# DC3402.net
KiCad netlist of a schematic drawn in EAGLE
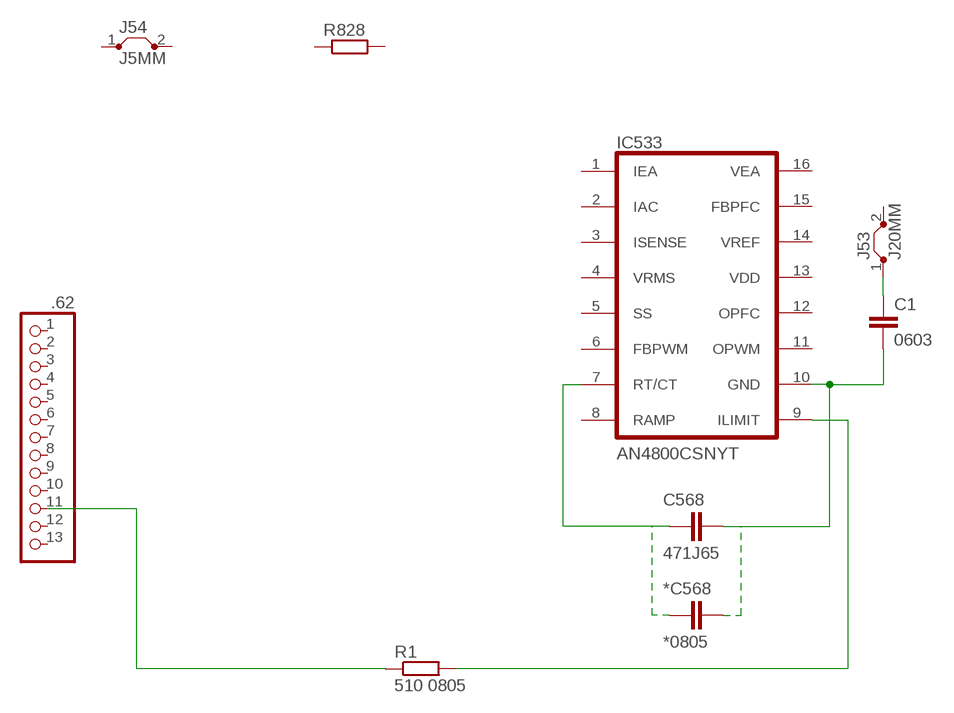
[diagram p0: schematic, sheet 1]

(export (version "E")
  (design (tool "Eeschema 10.0.6"))
  (components
    (comp (ref "*C568")
      (value "*0805")
      (footprint "eagle-import:C0805")
      (libsource (lib "eagle-import") (part "C-EUC0805"))
    )
    (comp (ref ".62")
      (value "PINHD-1X13/90")
      (footprint "eagle-import:1X13_90")
      (libsource (lib "eagle-import") (part "PINHD-1X13/90"))
    )
    (comp (ref "C1")
      (value "0603")
      (footprint "eagle-import:C0603")
      (libsource (lib "eagle-import") (part "C-EUC0603"))
    )
    (comp (ref "C568")
      (value "471J65")
      (footprint "eagle-import:C025-025X050")
      (libsource (lib "eagle-import") (part "C-EU025-025X050"))
    )
    (comp (ref "IC533")
      (value "AN4800CSNYT")
      (footprint "eagle-import:DIL16")
      (libsource (lib "eagle-import") (part "FAN4800"))
    )
    (comp (ref "J53")
      (value "J20MM")
      (footprint "eagle-import:20")
      (libsource (lib "eagle-import") (part "J20MM"))
    )
    (comp (ref "J54")
      (value "J5MM")
      (footprint "eagle-import:05")
      (libsource (lib "eagle-import") (part "J5MM"))
    )
    (comp (ref "R1")
      (value "510 0805")
      (footprint "eagle-import:R0805")
      (libsource (lib "eagle-import") (part "R-EU_R0805"))
    )
    (comp (ref "R828")
      (value "R-EU_0207/12")
      (footprint "eagle-import:0207_12")
      (libsource (lib "eagle-import") (part "R-EU_0207/12"))
    )
  )
  (nets
    (net (code "1") (name "Net-(.62-Pad11)") (class "Default")
      (node (ref ".62") (pin "11") (pinfunction "11_11") (pintype "passive"))
      (node (ref "R1") (pin "1") (pinfunction "1_1") (pintype "passive"))
    )
    (net (code "2") (name "Net-(C1-Pad1)") (class "Default")
      (node (ref "C1") (pin "1") (pinfunction "1_1") (pintype "passive"))
      (node (ref "J53") (pin "1") (pinfunction "1_1") (pintype "passive"))
    )
    (net (code "3") (name "Net-(IC533-GND)") (class "Default")
      (node (ref "*C568") (pin "2") (pinfunction "2_2") (pintype "passive"))
      (node (ref "C1") (pin "2") (pinfunction "2_2") (pintype "passive"))
      (node (ref "C568") (pin "2") (pinfunction "2_2") (pintype "passive"))
      (node (ref "IC533") (pin "10") (pinfunction "GND_10") (pintype "bidirectional"))
    )
    (net (code "4") (name "Net-(IC533-ILIMIT)") (class "Default")
      (node (ref "IC533") (pin "9") (pinfunction "ILIMIT_9") (pintype "bidirectional"))
      (node (ref "R1") (pin "2") (pinfunction "2_2") (pintype "passive"))
    )
    (net (code "5") (name "Net-(IC533-RT{slash}CT)") (class "Default")
      (node (ref "*C568") (pin "1") (pinfunction "1_1") (pintype "passive"))
      (node (ref "C568") (pin "1") (pinfunction "1_1") (pintype "passive"))
      (node (ref "IC533") (pin "7") (pinfunction "RT/CT_7") (pintype "bidirectional"))
    )
    (net (code "6") (name "unconnected-(.62-Pad1)") (class "Default")
      (node (ref ".62") (pin "1") (pinfunction "1_1") (pintype "passive"))
    )
    (net (code "7") (name "unconnected-(.62-Pad2)") (class "Default")
      (node (ref ".62") (pin "2") (pinfunction "2_2") (pintype "passive"))
    )
    (net (code "8") (name "unconnected-(.62-Pad3)") (class "Default")
      (node (ref ".62") (pin "3") (pinfunction "3_3") (pintype "passive"))
    )
    (net (code "9") (name "unconnected-(.62-Pad4)") (class "Default")
      (node (ref ".62") (pin "4") (pinfunction "4_4") (pintype "passive"))
    )
    (net (code "10") (name "unconnected-(.62-Pad5)") (class "Default")
      (node (ref ".62") (pin "5") (pinfunction "5_5") (pintype "passive"))
    )
    (net (code "11") (name "unconnected-(.62-Pad6)") (class "Default")
      (node (ref ".62") (pin "6") (pinfunction "6_6") (pintype "passive"))
    )
    (net (code "12") (name "unconnected-(.62-Pad7)") (class "Default")
      (node (ref ".62") (pin "7") (pinfunction "7_7") (pintype "passive"))
    )
    (net (code "13") (name "unconnected-(.62-Pad8)") (class "Default")
      (node (ref ".62") (pin "8") (pinfunction "8_8") (pintype "passive"))
    )
    (net (code "14") (name "unconnected-(.62-Pad9)") (class "Default")
      (node (ref ".62") (pin "9") (pinfunction "9_9") (pintype "passive"))
    )
    (net (code "15") (name "unconnected-(.62-Pad10)") (class "Default")
      (node (ref ".62") (pin "10") (pinfunction "10_10") (pintype "passive"))
    )
    (net (code "16") (name "unconnected-(.62-Pad12)") (class "Default")
      (node (ref ".62") (pin "12") (pinfunction "12_12") (pintype "passive"))
    )
    (net (code "17") (name "unconnected-(.62-Pad13)") (class "Default")
      (node (ref ".62") (pin "13") (pinfunction "13_13") (pintype "passive"))
    )
    (net (code "18") (name "unconnected-(IC533-FBPFC-Pad15)") (class "Default")
      (node (ref "IC533") (pin "15") (pinfunction "FBPFC_15") (pintype "bidirectional"))
    )
    (net (code "19") (name "unconnected-(IC533-FBPWM-Pad6)") (class "Default")
      (node (ref "IC533") (pin "6") (pinfunction "FBPWM_6") (pintype "bidirectional"))
    )
    (net (code "20") (name "unconnected-(IC533-IAC-Pad2)") (class "Default")
      (node (ref "IC533") (pin "2") (pinfunction "IAC_2") (pintype "bidirectional"))
    )
    (net (code "21") (name "unconnected-(IC533-IEA-Pad1)") (class "Default")
      (node (ref "IC533") (pin "1") (pinfunction "IEA_1") (pintype "bidirectional"))
    )
    (net (code "22") (name "unconnected-(IC533-ISENSE-Pad3)") (class "Default")
      (node (ref "IC533") (pin "3") (pinfunction "ISENSE_3") (pintype "bidirectional"))
    )
    (net (code "23") (name "unconnected-(IC533-OPFC-Pad12)") (class "Default")
      (node (ref "IC533") (pin "12") (pinfunction "OPFC_12") (pintype "bidirectional"))
    )
    (net (code "24") (name "unconnected-(IC533-OPWM-Pad11)") (class "Default")
      (node (ref "IC533") (pin "11") (pinfunction "OPWM_11") (pintype "bidirectional"))
    )
    (net (code "25") (name "unconnected-(IC533-RAMP-Pad8)") (class "Default")
      (node (ref "IC533") (pin "8") (pinfunction "RAMP_8") (pintype "bidirectional"))
    )
    (net (code "26") (name "unconnected-(IC533-SS-Pad5)") (class "Default")
      (node (ref "IC533") (pin "5") (pinfunction "SS_5") (pintype "bidirectional"))
    )
    (net (code "27") (name "unconnected-(IC533-VDD-Pad13)") (class "Default")
      (node (ref "IC533") (pin "13") (pinfunction "VDD_13") (pintype "bidirectional"))
    )
    (net (code "28") (name "unconnected-(IC533-VEA-Pad16)") (class "Default")
      (node (ref "IC533") (pin "16") (pinfunction "VEA_16") (pintype "bidirectional"))
    )
    (net (code "29") (name "unconnected-(IC533-VREF-Pad14)") (class "Default")
      (node (ref "IC533") (pin "14") (pinfunction "VREF_14") (pintype "bidirectional"))
    )
    (net (code "30") (name "unconnected-(IC533-VRMS-Pad4)") (class "Default")
      (node (ref "IC533") (pin "4") (pinfunction "VRMS_4") (pintype "bidirectional"))
    )
    (net (code "31") (name "unconnected-(J53-Pad2)") (class "Default")
      (node (ref "J53") (pin "2") (pinfunction "2_2") (pintype "passive"))
    )
    (net (code "32") (name "unconnected-(J54-Pad1)") (class "Default")
      (node (ref "J54") (pin "1") (pinfunction "1_1") (pintype "passive"))
    )
    (net (code "33") (name "unconnected-(J54-Pad2)") (class "Default")
      (node (ref "J54") (pin "2") (pinfunction "2_2") (pintype "passive"))
    )
    (net (code "34") (name "unconnected-(R828-Pad1)") (class "Default")
      (node (ref "R828") (pin "1") (pinfunction "1_1") (pintype "passive"))
    )
    (net (code "35") (name "unconnected-(R828-Pad2)") (class "Default")
      (node (ref "R828") (pin "2") (pinfunction "2_2") (pintype "passive"))
    )
  )
)
